# dashboard_controller.net
KiCad netlist of a schematic drawn in EAGLE
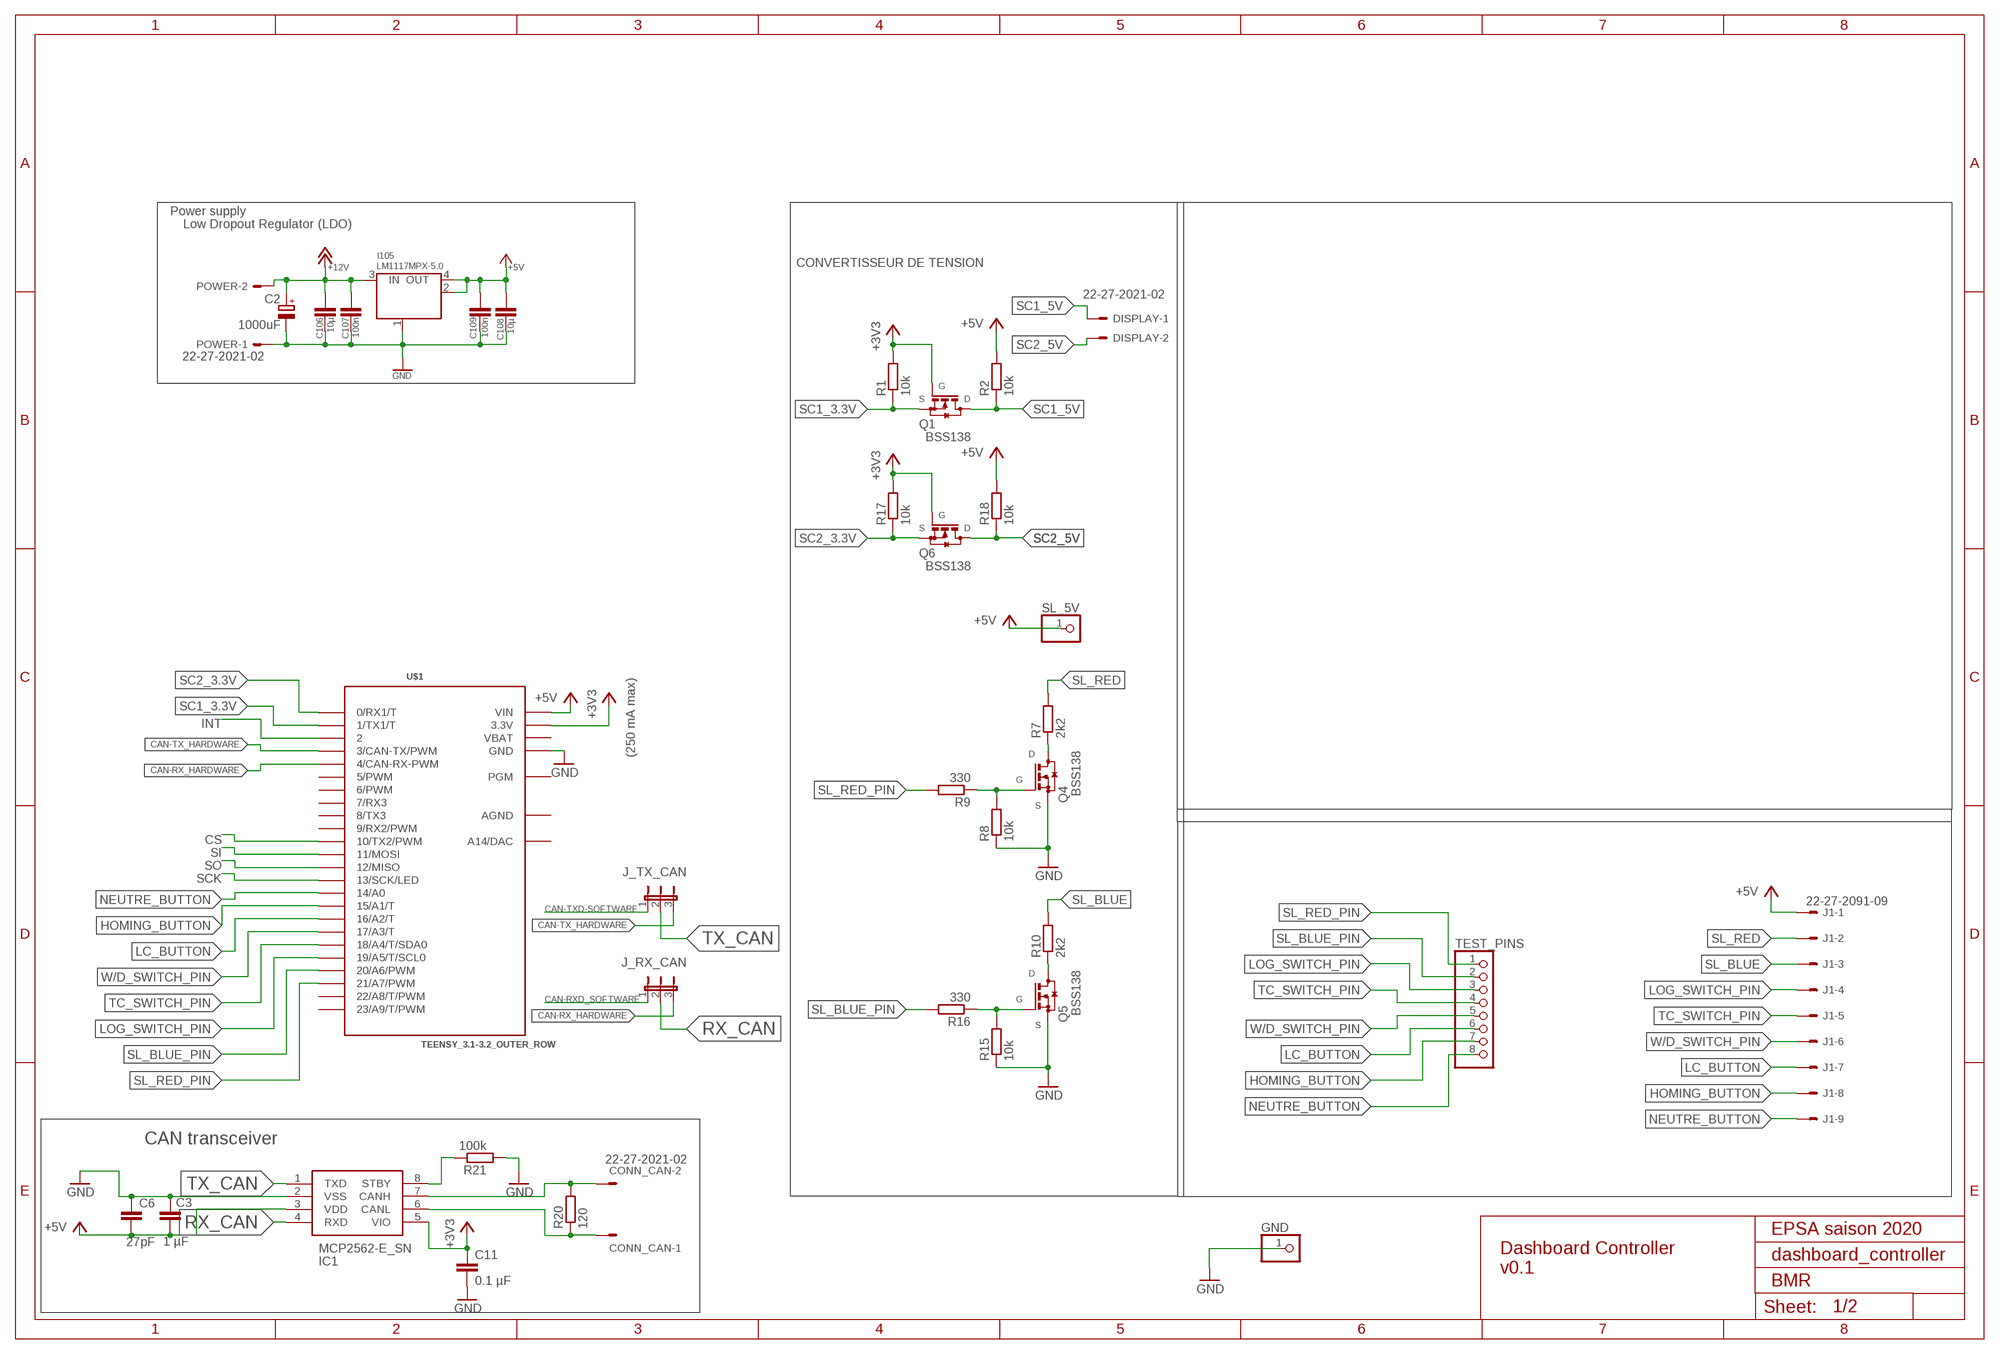
[diagram p0: schematic, sheet 1]
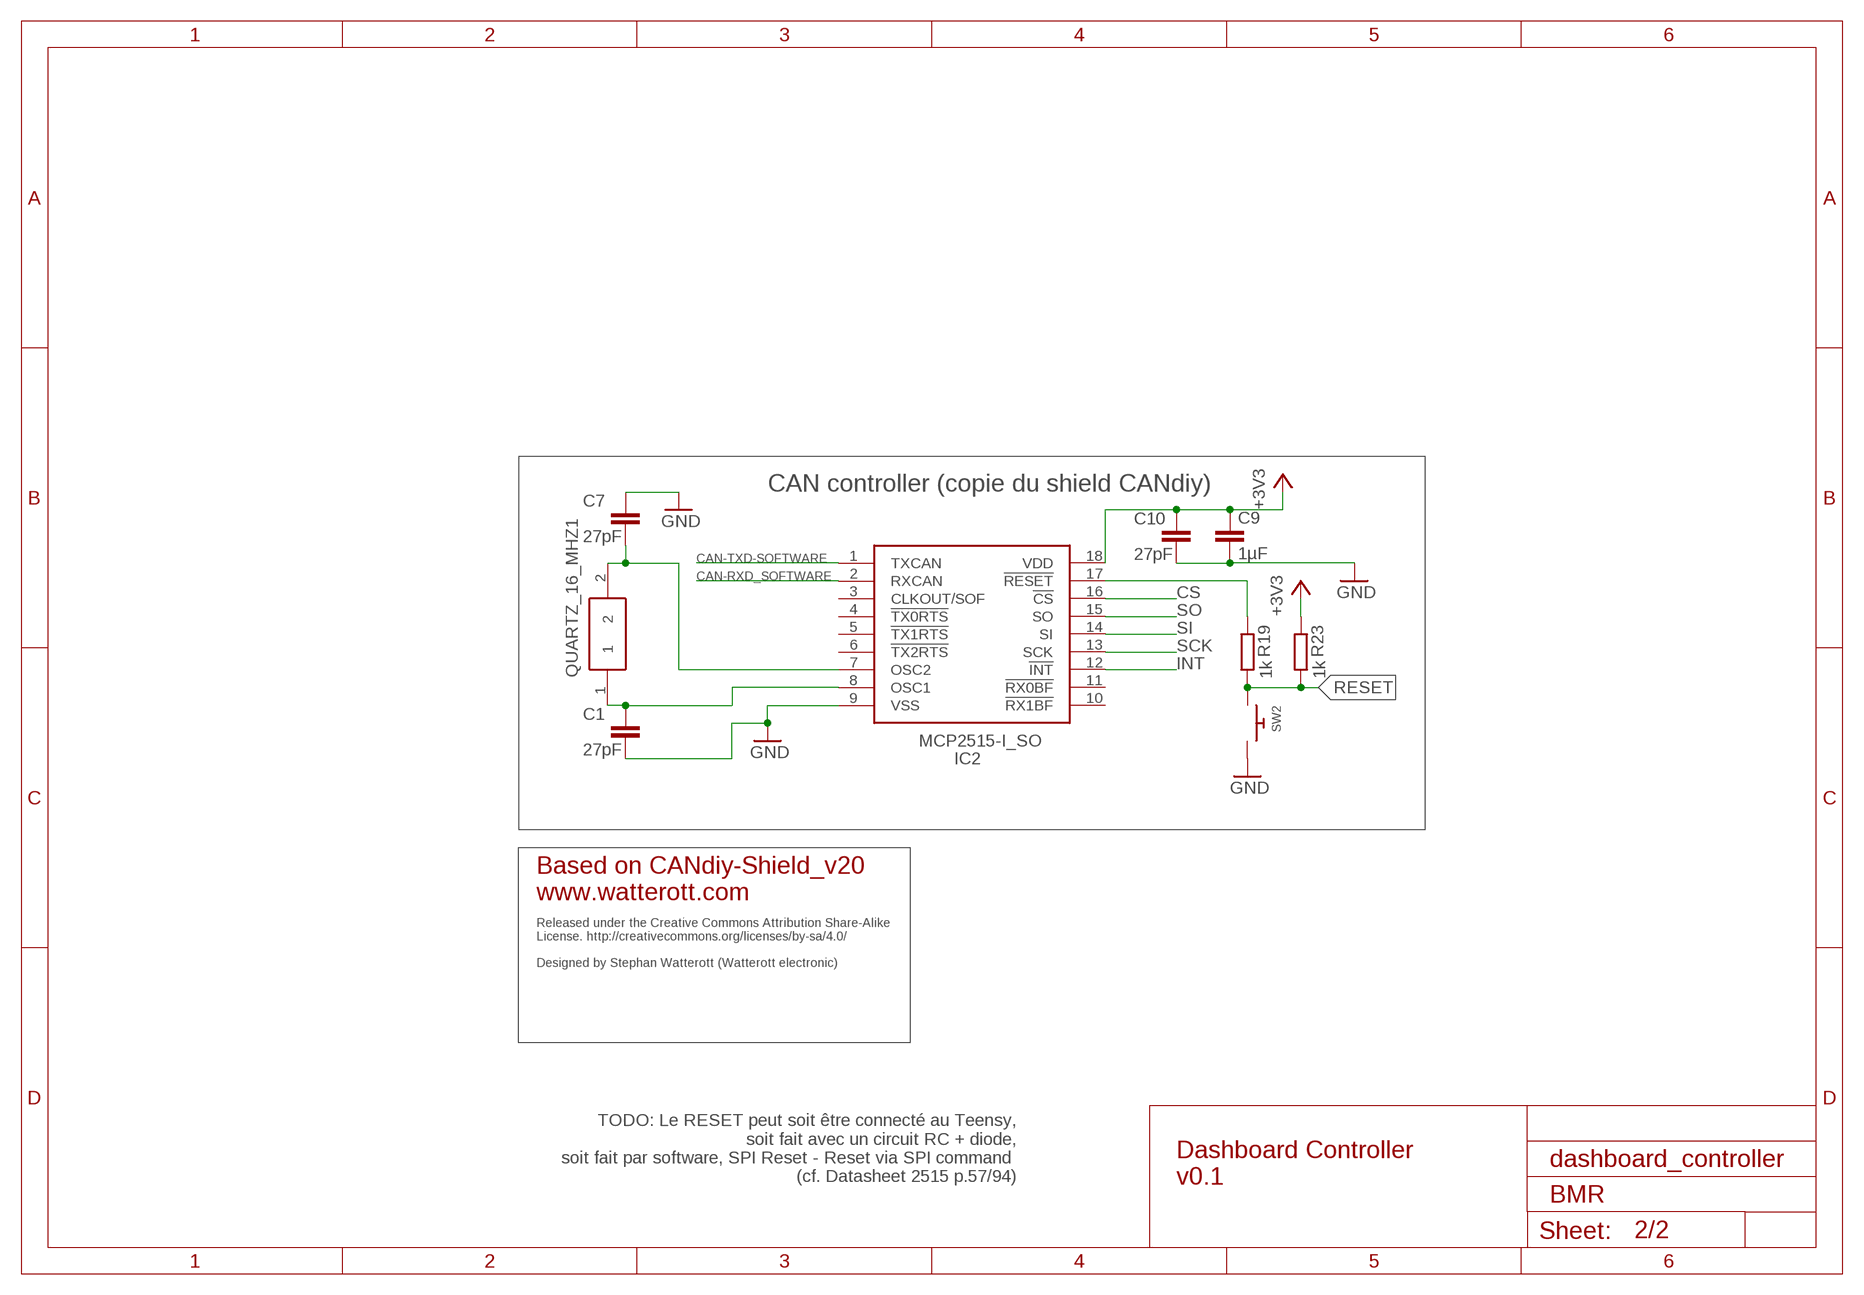
[diagram p1: schematic, sheet 2]

(export (version "E")
  (design (tool "Eeschema 10.0.6"))
  (components
    (comp (ref "C1")
      (value "27pF")
      (footprint "eagle-import:C0805")
      (libsource (lib "eagle-import") (part "rcl_334_C-EUC0805"))
    )
    (comp (ref "C7")
      (value "27pF")
      (footprint "eagle-import:C0805")
      (libsource (lib "eagle-import") (part "rcl_334_C-EUC0805"))
    )
    (comp (ref "C9")
      (value "1µF")
      (footprint "eagle-import:C0805")
      (libsource (lib "eagle-import") (part "rcl_334_C-EUC0805"))
    )
    (comp (ref "C10")
      (value "27pF")
      (footprint "eagle-import:C0805")
      (libsource (lib "eagle-import") (part "rcl_334_C-EUC0805"))
    )
    (comp (ref "IC2")
      (value "MCP2515-I_SO")
      (footprint "eagle-import:SOIC127P1030X265-18N")
      (fields
        (field (name "MANUFACTURER_PART_NUMBER") "MCP2515-I/SO")
        (field (name "RS_PART_NUMBER") "1445765")
      )
      (libsource (lib "eagle-import") (part "MCP2515-I_SO"))
    )
    (comp (ref "QUARTZ_16_MHZ1")
      (value "FOXSLF_160-20")
      (footprint "eagle-import:HC49SLF_1")
      (fields
        (field (name "MANUFACTURER_PART_NUMBER") "FOXSLF/160-20")
        (field (name "RS_PART_NUMBER") "1734298")
      )
      (libsource (lib "eagle-import") (part "FOXSLF_160-20"))
    )
    (comp (ref "R19")
      (value "1k")
      (footprint "eagle-import:R0805")
      (libsource (lib "eagle-import") (part "R-EU_R0805"))
    )
    (comp (ref "R23")
      (value "1k")
      (footprint "eagle-import:R0805")
      (libsource (lib "eagle-import") (part "R-EU_R0805"))
    )
    (comp (ref "SW2")
      (value "SWITCH_PUSHBUTTONEVQ-PE")
      (footprint "eagle-import:TACT_PANA-EVQ")
      (libsource (lib "eagle-import") (part "SWITCH_PUSHBUTTONEVQ-PE"))
    )
    (comp (ref "C2")
      (value "1000uF")
      (footprint "eagle-import:E25-10")
      (libsource (lib "eagle-import") (part "CPOL-EUE25-10AXIAL"))
    )
    (comp (ref "C3")
      (value "1 µF")
      (footprint "eagle-import:C0805")
      (libsource (lib "eagle-import") (part "rcl_334_C-EUC0805"))
    )
    (comp (ref "C6")
      (value "27pF")
      (footprint "eagle-import:C0805")
      (libsource (lib "eagle-import") (part "rcl_334_C-EUC0805"))
    )
    (comp (ref "C11")
      (value "0.1 µF")
      (footprint "eagle-import:C0805")
      (libsource (lib "eagle-import") (part "rcl_334_C-EUC0805"))
    )
    (comp (ref "C106")
      (value "10µ")
      (footprint "eagle-import:C0805")
      (libsource (lib "eagle-import") (part "rcl_334_C-EUC0805"))
    )
    (comp (ref "C107")
      (value "100n")
      (footprint "eagle-import:C0603")
      (libsource (lib "eagle-import") (part "C-EUC0603"))
    )
    (comp (ref "C108")
      (value "10µ")
      (footprint "eagle-import:C0805")
      (libsource (lib "eagle-import") (part "rcl_334_C-EUC0805"))
    )
    (comp (ref "C109")
      (value "100n")
      (footprint "eagle-import:C0603")
      (libsource (lib "eagle-import") (part "C-EUC0603"))
    )
    (comp (ref "CONN_CAN")
      (value "22-27-2021-02")
      (footprint "eagle-import:6410-02")
      (fields (field (name "MF") "MOLEX"))
      (libsource (lib "eagle-import") (part "22-?-0227-2021"))
    )
    (comp (ref "DISPLAY")
      (value "22-27-2021-02")
      (footprint "eagle-import:6410-02")
      (fields (field (name "MF") "MOLEX"))
      (libsource (lib "eagle-import") (part "22-?-0227-2021"))
    )
    (comp (ref "GND")
      (value "PINHD-1X1")
      (footprint "eagle-import:1X01")
      (libsource (lib "eagle-import") (part "PINHD-1X1"))
    )
    (comp (ref "I105")
      (value "LM1117MPX-5.0")
      (footprint "eagle-import:LINEAR_SOT223")
      (fields (field (name "PART_NUMBER") "LM1117IMPX-5.0"))
      (libsource (lib "eagle-import") (part "0022_LM1117IMPX-5.0"))
    )
    (comp (ref "IC1")
      (value "MCP2562-E_SN")
      (footprint "eagle-import:SOIC127P600X175-8N")
      (fields
        (field (name "MANUFACTURER_PART_NUMBER") "MCP2562-E/SN")
        (field (name "RS_PART_NUMBER") "7990228P")
      )
      (libsource (lib "eagle-import") (part "MCP2562-E_SN"))
    )
    (comp (ref "J1")
      (value "22-27-2091-09")
      (footprint "eagle-import:6410-09")
      (fields (field (name "MF") "MOLEX"))
      (libsource (lib "eagle-import") (part "22-?-0927-2091"))
    )
    (comp (ref "J_RX_CAN")
      (value "JP2E")
      (footprint "eagle-import:JP2")
      (libsource (lib "eagle-import") (part "JP2E"))
    )
    (comp (ref "J_TX_CAN")
      (value "JP2E")
      (footprint "eagle-import:JP2")
      (libsource (lib "eagle-import") (part "JP2E"))
    )
    (comp (ref "POWER")
      (value "22-27-2021-02")
      (footprint "eagle-import:6410-02")
      (fields (field (name "MF") "MOLEX"))
      (libsource (lib "eagle-import") (part "22-?-0227-2021"))
    )
    (comp (ref "Q1")
      (value "BSS138")
      (footprint "eagle-import:SOT23")
      (libsource (lib "eagle-import") (part "BSS123"))
    )
    (comp (ref "Q4")
      (value "BSS138")
      (footprint "eagle-import:SOT23")
      (libsource (lib "eagle-import") (part "BSS123"))
    )
    (comp (ref "Q5")
      (value "BSS138")
      (footprint "eagle-import:SOT23")
      (libsource (lib "eagle-import") (part "BSS123"))
    )
    (comp (ref "Q6")
      (value "BSS138")
      (footprint "eagle-import:SOT23")
      (libsource (lib "eagle-import") (part "BSS123"))
    )
    (comp (ref "R1")
      (value "10k")
      (footprint "eagle-import:R0805")
      (libsource (lib "eagle-import") (part "R-EU_R0805"))
    )
    (comp (ref "R2")
      (value "10k")
      (footprint "eagle-import:R0805")
      (libsource (lib "eagle-import") (part "R-EU_R0805"))
    )
    (comp (ref "R7")
      (value "2k2")
      (footprint "eagle-import:R0805")
      (libsource (lib "eagle-import") (part "R-EU_R0805"))
    )
    (comp (ref "R8")
      (value "10k")
      (footprint "eagle-import:R0805")
      (libsource (lib "eagle-import") (part "R-EU_R0805"))
    )
    (comp (ref "R9")
      (value "330")
      (footprint "eagle-import:R0805")
      (libsource (lib "eagle-import") (part "R-EU_R0805"))
    )
    (comp (ref "R10")
      (value "2k2")
      (footprint "eagle-import:R0805")
      (libsource (lib "eagle-import") (part "R-EU_R0805"))
    )
    (comp (ref "R15")
      (value "10k")
      (footprint "eagle-import:R0805")
      (libsource (lib "eagle-import") (part "R-EU_R0805"))
    )
    (comp (ref "R16")
      (value "330")
      (footprint "eagle-import:R0805")
      (libsource (lib "eagle-import") (part "R-EU_R0805"))
    )
    (comp (ref "R17")
      (value "10k")
      (footprint "eagle-import:R0805")
      (libsource (lib "eagle-import") (part "R-EU_R0805"))
    )
    (comp (ref "R18")
      (value "10k")
      (footprint "eagle-import:R0805")
      (libsource (lib "eagle-import") (part "R-EU_R0805"))
    )
    (comp (ref "R20")
      (value "120")
      (footprint "eagle-import:R0805")
      (libsource (lib "eagle-import") (part "R-EU_R0805"))
    )
    (comp (ref "R21")
      (value "100k")
      (footprint "eagle-import:R0805")
      (libsource (lib "eagle-import") (part "R-EU_R0805"))
    )
    (comp (ref "SL_5V")
      (value "PINHD-1X1")
      (footprint "eagle-import:1X01")
      (libsource (lib "eagle-import") (part "PINHD-1X1"))
    )
    (comp (ref "TEST_PINS")
      (value "PINHD-1X8")
      (footprint "eagle-import:1X08")
      (libsource (lib "eagle-import") (part "PINHD-1X8"))
    )
    (comp (ref "U$1")
      (value "TEENSY_3.1-3.2_OUTER_ROW")
      (footprint "eagle-import:TEENSY_3.0-3.2&LC_OUTER_ROW")
      (libsource (lib "eagle-import") (part "TEENSY_3.1-3.2_OUTER_ROW"))
    )
  )
  (nets
    (net (code "1") (name "+3V3") (class "Default")
      (node (ref "C10") (pin "1") (pinfunction "1_1") (pintype "passive"))
      (node (ref "C11") (pin "1") (pinfunction "1_1") (pintype "passive"))
      (node (ref "C9") (pin "1") (pinfunction "1_1") (pintype "passive"))
      (node (ref "IC1") (pin "5") (pinfunction "VIO_5") (pintype "bidirectional"))
      (node (ref "IC2") (pin "18") (pinfunction "VDD_18") (pintype "power_in"))
      (node (ref "Q1") (pin "1") (pinfunction "G_1") (pintype "passive"))
      (node (ref "Q6") (pin "1") (pinfunction "G_1") (pintype "passive"))
      (node (ref "R1") (pin "2") (pinfunction "2_2") (pintype "passive"))
      (node (ref "R17") (pin "2") (pinfunction "2_2") (pintype "passive"))
      (node (ref "R23") (pin "1") (pinfunction "1_1") (pintype "passive"))
      (node (ref "U$1") (pin "3.3V") (pinfunction "3.3V_3.3V") (pintype "power_in"))
      (node (ref "U$1") (pin "3.3V1") (pinfunction "3.3V_3.3V1") (pintype "power_in"))
    )
    (net (code "2") (name "+5V") (class "Default")
      (node (ref "C108") (pin "1") (pinfunction "1_1") (pintype "passive"))
      (node (ref "C109") (pin "2") (pinfunction "2_2") (pintype "passive"))
      (node (ref "C3") (pin "2") (pinfunction "2_2") (pintype "passive"))
      (node (ref "C6") (pin "2") (pinfunction "2_2") (pintype "passive"))
      (node (ref "I105") (pin "2") (pinfunction "OUT_2") (pintype "passive"))
      (node (ref "I105") (pin "4") (pinfunction "OUT_4") (pintype "passive"))
      (node (ref "IC1") (pin "3") (pinfunction "VDD_3") (pintype "bidirectional"))
      (node (ref "J1") (pin "1") (pinfunction "S_1") (pintype "passive"))
      (node (ref "R18") (pin "2") (pinfunction "2_2") (pintype "passive"))
      (node (ref "R2") (pin "2") (pinfunction "2_2") (pintype "passive"))
      (node (ref "SL_5V") (pin "1") (pinfunction "1_1") (pintype "passive"))
      (node (ref "U$1") (pin "VIN") (pinfunction "VIN_VIN") (pintype "power_in"))
    )
    (net (code "3") (name "+12V") (class "Default")
      (node (ref "C106") (pin "1") (pinfunction "1_1") (pintype "passive"))
      (node (ref "C107") (pin "1") (pinfunction "1_1") (pintype "passive"))
      (node (ref "C2") (pin "+") (pinfunction "+_+") (pintype "passive"))
      (node (ref "I105") (pin "3") (pinfunction "IN_3") (pintype "input"))
      (node (ref "POWER") (pin "2") (pinfunction "S_2") (pintype "passive"))
    )
    (net (code "4") (name "AGND") (class "Default")
      (node (ref "U$1") (pin "AGND") (pinfunction "AGND_AGND") (pintype "power_in"))
    )
    (net (code "5") (name "CAN-RXD_SOFTWARE") (class "Default")
      (node (ref "IC2") (pin "2") (pinfunction "RXCAN_2") (pintype "bidirectional"))
      (node (ref "J_RX_CAN") (pin "1") (pinfunction "1_1") (pintype "passive"))
    )
    (net (code "6") (name "CAN-RX_HARDWARE") (class "Default")
      (node (ref "J_RX_CAN") (pin "3") (pinfunction "3_3") (pintype "passive"))
      (node (ref "U$1") (pin "4") (pinfunction "4/CAN-RX-PWM_4") (pintype "bidirectional"))
    )
    (net (code "7") (name "CAN-TXD-SOFTWARE") (class "Default")
      (node (ref "IC2") (pin "1") (pinfunction "TXCAN_1") (pintype "bidirectional"))
      (node (ref "J_TX_CAN") (pin "1") (pinfunction "1_1") (pintype "passive"))
    )
    (net (code "8") (name "CAN-TX_HARDWARE") (class "Default")
      (node (ref "J_TX_CAN") (pin "3") (pinfunction "3_3") (pintype "passive"))
      (node (ref "U$1") (pin "3") (pinfunction "3/CAN-TX/PWM_3") (pintype "bidirectional"))
    )
    (net (code "9") (name "CS") (class "Default")
      (node (ref "IC2") (pin "16") (pinfunction "~{CS}_16") (pintype "input"))
      (node (ref "U$1") (pin "10") (pinfunction "10/TX2/PWM_10") (pintype "bidirectional"))
    )
    (net (code "10") (name "GND") (class "Default")
      (node (ref "C1") (pin "2") (pinfunction "2_2") (pintype "passive"))
      (node (ref "C10") (pin "2") (pinfunction "2_2") (pintype "passive"))
      (node (ref "C106") (pin "2") (pinfunction "2_2") (pintype "passive"))
      (node (ref "C107") (pin "2") (pinfunction "2_2") (pintype "passive"))
      (node (ref "C108") (pin "2") (pinfunction "2_2") (pintype "passive"))
      (node (ref "C109") (pin "1") (pinfunction "1_1") (pintype "passive"))
      (node (ref "C11") (pin "2") (pinfunction "2_2") (pintype "passive"))
      (node (ref "C2") (pin "-") (pinfunction "-_-") (pintype "passive"))
      (node (ref "C3") (pin "1") (pinfunction "1_1") (pintype "passive"))
      (node (ref "C6") (pin "1") (pinfunction "1_1") (pintype "passive"))
      (node (ref "C7") (pin "1") (pinfunction "1_1") (pintype "passive"))
      (node (ref "C9") (pin "2") (pinfunction "2_2") (pintype "passive"))
      (node (ref "GND") (pin "1") (pinfunction "1_1") (pintype "passive"))
      (node (ref "I105") (pin "1") (pinfunction "GND/ADJ_1") (pintype "input"))
      (node (ref "IC1") (pin "2") (pinfunction "VSS_2") (pintype "bidirectional"))
      (node (ref "IC2") (pin "9") (pinfunction "VSS_9") (pintype "power_in"))
      (node (ref "POWER") (pin "1") (pinfunction "S_1") (pintype "passive"))
      (node (ref "Q4") (pin "2") (pinfunction "S_2") (pintype "passive"))
      (node (ref "Q5") (pin "2") (pinfunction "S_2") (pintype "passive"))
      (node (ref "R15") (pin "1") (pinfunction "1_1") (pintype "passive"))
      (node (ref "R21") (pin "1") (pinfunction "1_1") (pintype "passive"))
      (node (ref "R8") (pin "1") (pinfunction "1_1") (pintype "passive"))
      (node (ref "SW2") (pin "P$2") (pinfunction "P$2_P$2") (pintype "passive"))
      (node (ref "U$1") (pin "GND") (pinfunction "GND_GND") (pintype "power_in"))
      (node (ref "U$1") (pin "GND1") (pinfunction "GND_GND1") (pintype "power_in"))
    )
    (net (code "11") (name "HOMING_BUTTON") (class "Default")
      (node (ref "J1") (pin "8") (pinfunction "S_8") (pintype "passive"))
      (node (ref "TEST_PINS") (pin "7") (pinfunction "7_7") (pintype "passive"))
      (node (ref "U$1") (pin "15/A1") (pinfunction "15/A1/T_15/A1") (pintype "bidirectional"))
    )
    (net (code "12") (name "INT") (class "Default")
      (node (ref "IC2") (pin "12") (pinfunction "~{INT}_12") (pintype "input"))
      (node (ref "U$1") (pin "2") (pinfunction "2_2") (pintype "bidirectional"))
    )
    (net (code "13") (name "LC_BUTTON") (class "Default")
      (node (ref "J1") (pin "7") (pinfunction "S_7") (pintype "passive"))
      (node (ref "TEST_PINS") (pin "6") (pinfunction "6_6") (pintype "passive"))
      (node (ref "U$1") (pin "16/A2") (pinfunction "16/A2/T_16/A2") (pintype "bidirectional"))
    )
    (net (code "14") (name "LOG_SWITCH_PIN") (class "Default")
      (node (ref "J1") (pin "4") (pinfunction "S_4") (pintype "passive"))
      (node (ref "TEST_PINS") (pin "3") (pinfunction "3_3") (pintype "passive"))
      (node (ref "U$1") (pin "19/A5") (pinfunction "19/A5/T/SCL0_19/A5") (pintype "bidirectional"))
    )
    (net (code "15") (name "NEUTRE_BUTTON") (class "Default")
      (node (ref "J1") (pin "9") (pinfunction "S_9") (pintype "passive"))
      (node (ref "TEST_PINS") (pin "8") (pinfunction "8_8") (pintype "passive"))
      (node (ref "U$1") (pin "14/A0") (pinfunction "14/A0_14/A0") (pintype "bidirectional"))
    )
    (net (code "16") (name "Net-(CONN_CANA-S)") (class "Default")
      (node (ref "CONN_CAN") (pin "1") (pinfunction "S_1") (pintype "passive"))
      (node (ref "IC1") (pin "6") (pinfunction "CANL_6") (pintype "bidirectional"))
      (node (ref "R20") (pin "1") (pinfunction "1_1") (pintype "passive"))
    )
    (net (code "17") (name "Net-(CONN_CANB-S)") (class "Default")
      (node (ref "CONN_CAN") (pin "2") (pinfunction "S_2") (pintype "passive"))
      (node (ref "IC1") (pin "7") (pinfunction "CANH_7") (pintype "bidirectional"))
      (node (ref "R20") (pin "2") (pinfunction "2_2") (pintype "passive"))
    )
    (net (code "18") (name "Net-(IC1-STBY)") (class "Default")
      (node (ref "IC1") (pin "8") (pinfunction "STBY_8") (pintype "bidirectional"))
      (node (ref "R21") (pin "2") (pinfunction "2_2") (pintype "passive"))
    )
    (net (code "19") (name "Net-(IC2-OSC1)") (class "Default")
      (node (ref "C1") (pin "1") (pinfunction "1_1") (pintype "passive"))
      (node (ref "IC2") (pin "8") (pinfunction "OSC1_8") (pintype "bidirectional"))
      (node (ref "QUARTZ_16_MHZ1") (pin "1") (pinfunction "1_1") (pintype "bidirectional"))
    )
    (net (code "20") (name "Net-(IC2-OSC2)") (class "Default")
      (node (ref "C7") (pin "2") (pinfunction "2_2") (pintype "passive"))
      (node (ref "IC2") (pin "7") (pinfunction "OSC2_7") (pintype "bidirectional"))
      (node (ref "QUARTZ_16_MHZ1") (pin "2") (pinfunction "2_2") (pintype "bidirectional"))
    )
    (net (code "21") (name "Net-(IC2-~{RESET})") (class "Default")
      (node (ref "IC2") (pin "17") (pinfunction "~{RESET}_17") (pintype "bidirectional"))
      (node (ref "R19") (pin "1") (pinfunction "1_1") (pintype "passive"))
    )
    (net (code "22") (name "Net-(Q4-D)") (class "Default")
      (node (ref "Q4") (pin "3") (pinfunction "D_3") (pintype "passive"))
      (node (ref "R7") (pin "1") (pinfunction "1_1") (pintype "passive"))
    )
    (net (code "23") (name "Net-(Q4-G)") (class "Default")
      (node (ref "Q4") (pin "1") (pinfunction "G_1") (pintype "passive"))
      (node (ref "R8") (pin "2") (pinfunction "2_2") (pintype "passive"))
      (node (ref "R9") (pin "1") (pinfunction "1_1") (pintype "passive"))
    )
    (net (code "24") (name "Net-(Q5-D)") (class "Default")
      (node (ref "Q5") (pin "3") (pinfunction "D_3") (pintype "passive"))
      (node (ref "R10") (pin "1") (pinfunction "1_1") (pintype "passive"))
    )
    (net (code "25") (name "Net-(Q5-G)") (class "Default")
      (node (ref "Q5") (pin "1") (pinfunction "G_1") (pintype "passive"))
      (node (ref "R15") (pin "2") (pinfunction "2_2") (pintype "passive"))
      (node (ref "R16") (pin "1") (pinfunction "1_1") (pintype "passive"))
    )
    (net (code "26") (name "RESET") (class "Default")
      (node (ref "R19") (pin "2") (pinfunction "2_2") (pintype "passive"))
      (node (ref "R23") (pin "2") (pinfunction "2_2") (pintype "passive"))
      (node (ref "SW2") (pin "P$1") (pinfunction "P$1_P$1") (pintype "passive"))
    )
    (net (code "27") (name "RX_CAN") (class "Default")
      (node (ref "IC1") (pin "4") (pinfunction "RXD_4") (pintype "bidirectional"))
      (node (ref "J_RX_CAN") (pin "2") (pinfunction "2_2") (pintype "passive"))
    )
    (net (code "28") (name "SC1_3.3V") (class "Default")
      (node (ref "Q1") (pin "2") (pinfunction "S_2") (pintype "passive"))
      (node (ref "R1") (pin "1") (pinfunction "1_1") (pintype "passive"))
      (node (ref "U$1") (pin "1") (pinfunction "1/TX1/T_1") (pintype "bidirectional"))
    )
    (net (code "29") (name "SC1_5V") (class "Default")
      (node (ref "DISPLAY") (pin "1") (pinfunction "S_1") (pintype "passive"))
      (node (ref "Q1") (pin "3") (pinfunction "D_3") (pintype "passive"))
      (node (ref "R2") (pin "1") (pinfunction "1_1") (pintype "passive"))
    )
    (net (code "30") (name "SC2_3.3V") (class "Default")
      (node (ref "Q6") (pin "2") (pinfunction "S_2") (pintype "passive"))
      (node (ref "R17") (pin "1") (pinfunction "1_1") (pintype "passive"))
      (node (ref "U$1") (pin "0") (pinfunction "0/RX1/T_0") (pintype "bidirectional"))
    )
    (net (code "31") (name "SC2_5V") (class "Default")
      (node (ref "DISPLAY") (pin "2") (pinfunction "S_2") (pintype "passive"))
      (node (ref "Q6") (pin "3") (pinfunction "D_3") (pintype "passive"))
      (node (ref "R18") (pin "1") (pinfunction "1_1") (pintype "passive"))
    )
    (net (code "32") (name "SCK") (class "Default")
      (node (ref "IC2") (pin "13") (pinfunction "SCK_13") (pintype "bidirectional"))
      (node (ref "U$1") (pin "13") (pinfunction "13/SCK/LED_13") (pintype "bidirectional"))
    )
    (net (code "33") (name "SI") (class "Default")
      (node (ref "IC2") (pin "14") (pinfunction "SI_14") (pintype "bidirectional"))
      (node (ref "U$1") (pin "11") (pinfunction "11/MOSI_11") (pintype "bidirectional"))
    )
    (net (code "34") (name "SL_BLUE") (class "Default")
      (node (ref "J1") (pin "3") (pinfunction "S_3") (pintype "passive"))
      (node (ref "R10") (pin "2") (pinfunction "2_2") (pintype "passive"))
    )
    (net (code "35") (name "SL_BLUE_PIN") (class "Default")
      (node (ref "R16") (pin "2") (pinfunction "2_2") (pintype "passive"))
      (node (ref "TEST_PINS") (pin "2") (pinfunction "2_2") (pintype "passive"))
      (node (ref "U$1") (pin "20/A6") (pinfunction "20/A6/PWM_20/A6") (pintype "bidirectional"))
    )
    (net (code "36") (name "SL_RED") (class "Default")
      (node (ref "J1") (pin "2") (pinfunction "S_2") (pintype "passive"))
      (node (ref "R7") (pin "2") (pinfunction "2_2") (pintype "passive"))
    )
    (net (code "37") (name "SL_RED_PIN") (class "Default")
      (node (ref "R9") (pin "2") (pinfunction "2_2") (pintype "passive"))
      (node (ref "TEST_PINS") (pin "1") (pinfunction "1_1") (pintype "passive"))
      (node (ref "U$1") (pin "21/A7") (pinfunction "21/A7/PWM_21/A7") (pintype "bidirectional"))
    )
    (net (code "38") (name "SO") (class "Default")
      (node (ref "IC2") (pin "15") (pinfunction "SO_15") (pintype "bidirectional"))
      (node (ref "U$1") (pin "12") (pinfunction "12/MISO_12") (pintype "bidirectional"))
    )
    (net (code "39") (name "TC_SWITCH_PIN") (class "Default")
      (node (ref "J1") (pin "5") (pinfunction "S_5") (pintype "passive"))
      (node (ref "TEST_PINS") (pin "4") (pinfunction "4_4") (pintype "passive"))
      (node (ref "U$1") (pin "18/A4") (pinfunction "18/A4/T/SDA0_18/A4") (pintype "bidirectional"))
    )
    (net (code "40") (name "TX_CAN") (class "Default")
      (node (ref "IC1") (pin "1") (pinfunction "TXD_1") (pintype "bidirectional"))
      (node (ref "J_TX_CAN") (pin "2") (pinfunction "2_2") (pintype "passive"))
    )
    (net (code "41") (name "VBAT") (class "Default")
      (node (ref "U$1") (pin "VBAT") (pinfunction "VBAT_VBAT") (pintype "power_in"))
    )
    (net (code "42") (name "W{slash}D_SWITCH_PIN") (class "Default")
      (node (ref "J1") (pin "6") (pinfunction "S_6") (pintype "passive"))
      (node (ref "TEST_PINS") (pin "5") (pinfunction "5_5") (pintype "passive"))
      (node (ref "U$1") (pin "17/A3") (pinfunction "17/A3/T_17/A3") (pintype "bidirectional"))
    )
    (net (code "43") (name "unconnected-(IC2-CLKOUT{slash}SOF-Pad3)") (class "Default")
      (node (ref "IC2") (pin "3") (pinfunction "CLKOUT/SOF_3") (pintype "output"))
    )
    (net (code "44") (name "unconnected-(IC2-~{RX0BF}-Pad11)") (class "Default")
      (node (ref "IC2") (pin "11") (pinfunction "~{RX0BF}_11") (pintype "bidirectional"))
    )
    (net (code "45") (name "unconnected-(IC2-~{RX1BF}-Pad10)") (class "Default")
      (node (ref "IC2") (pin "10") (pinfunction "~{RX1BF}_10") (pintype "bidirectional"))
    )
    (net (code "46") (name "unconnected-(IC2-~{TX0RTS}-Pad4)") (class "Default")
      (node (ref "IC2") (pin "4") (pinfunction "~{TX0RTS}_4") (pintype "bidirectional"))
    )
    (net (code "47") (name "unconnected-(IC2-~{TX1RTS}-Pad5)") (class "Default")
      (node (ref "IC2") (pin "5") (pinfunction "~{TX1RTS}_5") (pintype "bidirectional"))
    )
    (net (code "48") (name "unconnected-(IC2-~{TX2RTS}-Pad6)") (class "Default")
      (node (ref "IC2") (pin "6") (pinfunction "~{TX2RTS}_6") (pintype "bidirectional"))
    )
    (net (code "49") (name "unconnected-(U$1-5{slash}PWM-Pad5)") (class "Default")
      (node (ref "U$1") (pin "5") (pinfunction "5/PWM_5") (pintype "bidirectional"))
    )
    (net (code "50") (name "unconnected-(U$1-6{slash}PWM-Pad6)") (class "Default")
      (node (ref "U$1") (pin "6") (pinfunction "6/PWM_6") (pintype "bidirectional"))
    )
    (net (code "51") (name "unconnected-(U$1-7{slash}RX3-Pad7)") (class "Default")
      (node (ref "U$1") (pin "7") (pinfunction "7/RX3_7") (pintype "bidirectional"))
    )
    (net (code "52") (name "unconnected-(U$1-8{slash}TX3-Pad8)") (class "Default")
      (node (ref "U$1") (pin "8") (pinfunction "8/TX3_8") (pintype "bidirectional"))
    )
    (net (code "53") (name "unconnected-(U$1-9{slash}RX2{slash}PWM-Pad9)") (class "Default")
      (node (ref "U$1") (pin "9") (pinfunction "9/RX2/PWM_9") (pintype "bidirectional"))
    )
    (net (code "54") (name "unconnected-(U$1-22{slash}A8{slash}T{slash}PWM-Pad22{slash}A8)") (class "Default")
      (node (ref "U$1") (pin "22/A8") (pinfunction "22/A8/T/PWM_22/A8") (pintype "bidirectional"))
    )
    (net (code "55") (name "unconnected-(U$1-23{slash}A9{slash}T{slash}PWM-Pad23{slash}A9)") (class "Default")
      (node (ref "U$1") (pin "23/A9") (pinfunction "23/A9/T/PWM_23/A9") (pintype "bidirectional"))
    )
    (net (code "56") (name "unconnected-(U$1-A14{slash}DAC-PadRESET{slash}DAC)") (class "Default")
      (node (ref "U$1") (pin "RESET/DAC") (pinfunction "A14/DAC_RESET/DAC") (pintype "bidirectional"))
    )
    (net (code "57") (name "unconnected-(U$1-PadPGM)") (class "Default")
      (node (ref "U$1") (pin "PGM") (pinfunction "PGM_PGM") (pintype "bidirectional"))
    )
  )
)
